# ZHSD-PL-CONNS.net
KiCad netlist of a schematic drawn in Altium Designer
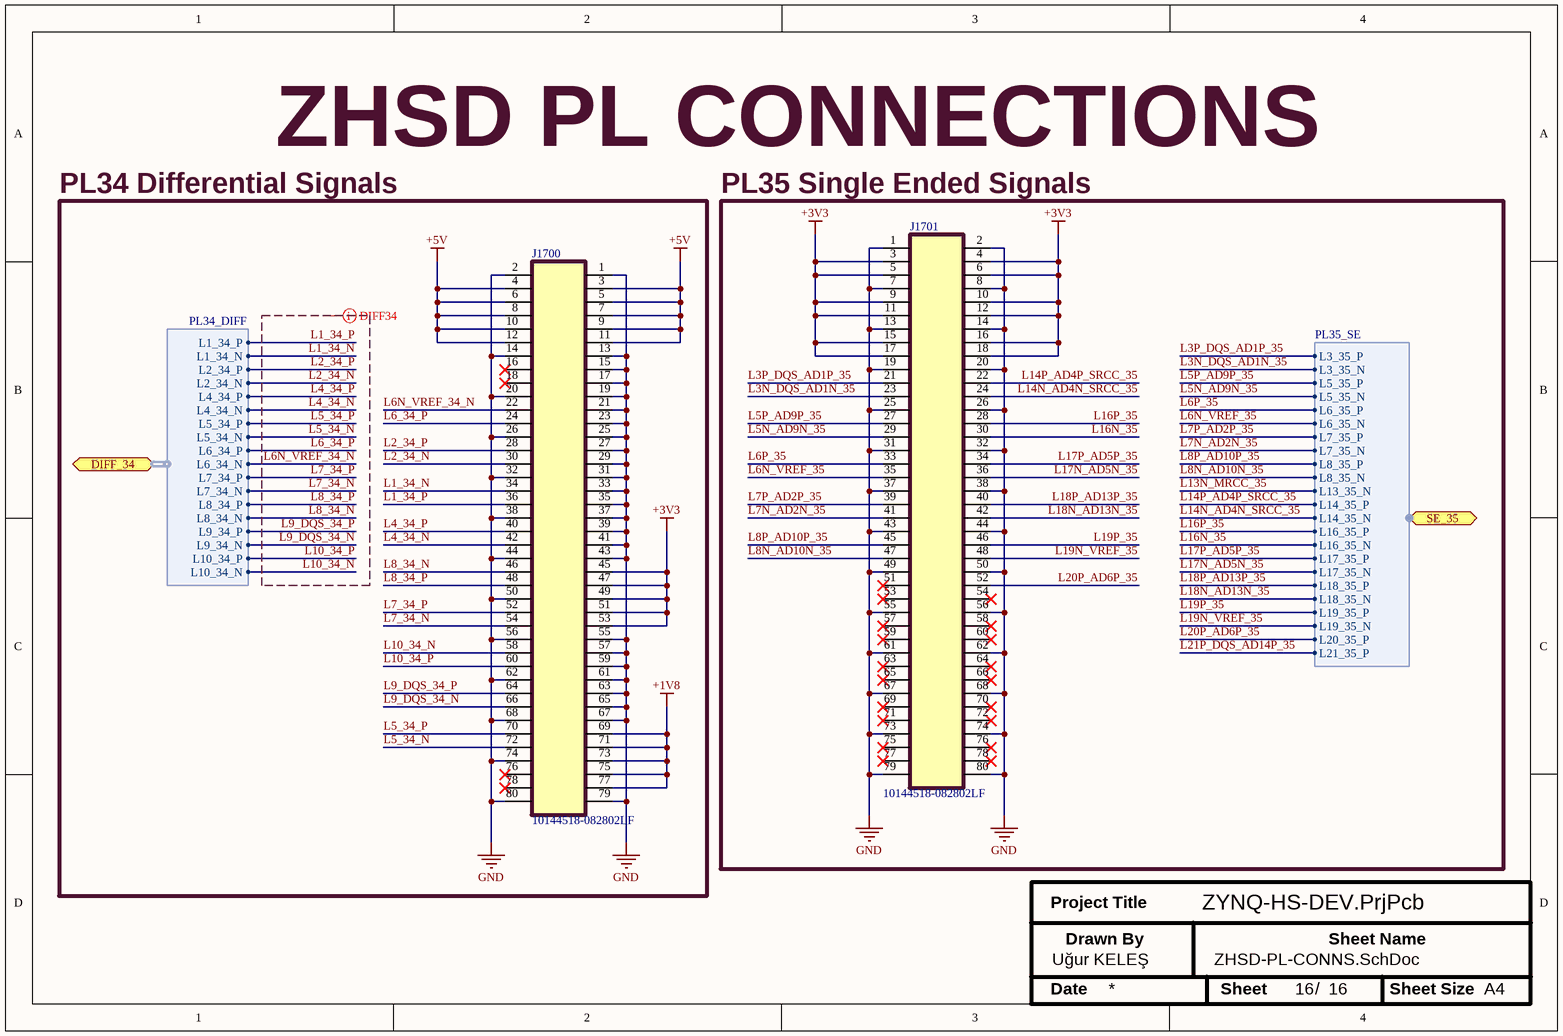
[diagram p0: ZHSD-PL-CONNS.SchDoc]

(export (version "E")
  (design (tool "Eeschema 10.0.6"))
  (components
    (comp (ref "J1700")
      (value "10144518-082802LF")
      (footprint "10144518-082802LF")
      (description "BergStak® Lite 0.80mm, Board-to-Board Connector, 80 Positions, Dual Row, Vertical Header")
      (fields (field (name "MANUFACTURER") "Amphenol"))
      (libsource (lib "") (part "10144518-082802LF_1"))
    )
    (comp (ref "J1701")
      (value "10144518-082802LF")
      (footprint "10144518-082802LF")
      (description "BergStak® Lite 0.80mm, Board-to-Board Connector, 80 Positions, Dual Row, Vertical Header")
      (fields (field (name "MANUFACTURER") "Amphenol"))
      (libsource (lib "UK_Library") (part "10144518-082802LF"))
    )
  )
  (nets
    (net (code "3") (name "+1V8") (class "Default")
      (node (ref "J1700") (pin "69") (pintype "passive"))
      (node (ref "J1700") (pin "71") (pintype "passive"))
      (node (ref "J1700") (pin "73") (pintype "passive"))
      (node (ref "J1700") (pin "75") (pintype "passive"))
      (node (ref "J1700") (pin "77") (pintype "passive"))
    )
    (net (code "4") (name "+3V3") (class "Default")
      (node (ref "J1700") (pin "45") (pintype "passive"))
      (node (ref "J1700") (pin "47") (pintype "passive"))
      (node (ref "J1700") (pin "49") (pintype "passive"))
      (node (ref "J1700") (pin "51") (pintype "passive"))
      (node (ref "J1700") (pin "53") (pintype "passive"))
      (node (ref "J1701") (pin "10") (pintype "passive"))
      (node (ref "J1701") (pin "11") (pintype "passive"))
      (node (ref "J1701") (pin "12") (pintype "passive"))
      (node (ref "J1701") (pin "15") (pintype "passive"))
      (node (ref "J1701") (pin "16") (pintype "passive"))
      (node (ref "J1701") (pin "17") (pintype "passive"))
      (node (ref "J1701") (pin "18") (pintype "passive"))
      (node (ref "J1701") (pin "3") (pintype "passive"))
      (node (ref "J1701") (pin "4") (pintype "passive"))
      (node (ref "J1701") (pin "5") (pintype "passive"))
      (node (ref "J1701") (pin "6") (pintype "passive"))
      (node (ref "J1701") (pin "9") (pintype "passive"))
    )
    (net (code "5") (name "+5V") (class "Default")
      (node (ref "J1700") (pin "10") (pintype "passive"))
      (node (ref "J1700") (pin "11") (pintype "passive"))
      (node (ref "J1700") (pin "12") (pintype "passive"))
      (node (ref "J1700") (pin "3") (pintype "passive"))
      (node (ref "J1700") (pin "4") (pintype "passive"))
      (node (ref "J1700") (pin "5") (pintype "passive"))
      (node (ref "J1700") (pin "6") (pintype "passive"))
      (node (ref "J1700") (pin "7") (pintype "passive"))
      (node (ref "J1700") (pin "8") (pintype "passive"))
      (node (ref "J1700") (pin "9") (pintype "passive"))
    )
    (net (code "6") (name "/L1_34_N") (class "Default") (node (ref "J1700") (pin "34") (pintype "passive")))
    (net (code "7") (name "/L1_34_P") (class "Default") (node (ref "J1700") (pin "36") (pintype "passive")))
    (net (code "8") (name "/L2_34_N") (class "Default") (node (ref "J1700") (pin "30") (pintype "passive")))
    (net (code "9") (name "/L2_34_P") (class "Default") (node (ref "J1700") (pin "28") (pintype "passive")))
    (net (code "10") (name "/L3N_DQS_AD1N_35") (class "Default")
      (node (ref "J1701") (pin "23") (pintype "passive"))
    )
    (net (code "11") (name "/L3P_DQS_AD1P_35") (class "Default")
      (node (ref "J1701") (pin "21") (pintype "passive"))
    )
    (net (code "12") (name "/L4_34_N") (class "Default") (node (ref "J1700") (pin "42") (pintype "passive")))
    (net (code "13") (name "/L4_34_P") (class "Default") (node (ref "J1700") (pin "40") (pintype "passive")))
    (net (code "14") (name "/L5N_AD9N_35") (class "Default")
      (node (ref "J1701") (pin "29") (pintype "passive"))
    )
    (net (code "15") (name "/L5P_AD9P_35") (class "Default")
      (node (ref "J1701") (pin "27") (pintype "passive"))
    )
    (net (code "16") (name "/L5_34_N") (class "Default") (node (ref "J1700") (pin "72") (pintype "passive")))
    (net (code "17") (name "/L5_34_P") (class "Default") (node (ref "J1700") (pin "70") (pintype "passive")))
    (net (code "18") (name "/L6N_VREF_34_N") (class "Default")
      (node (ref "J1700") (pin "22") (pintype "passive"))
    )
    (net (code "19") (name "/L6N_VREF_35") (class "Default")
      (node (ref "J1701") (pin "35") (pintype "passive"))
    )
    (net (code "20") (name "/L6P_35") (class "Default") (node (ref "J1701") (pin "33") (pintype "passive")))
    (net (code "21") (name "/L6_34_P") (class "Default") (node (ref "J1700") (pin "24") (pintype "passive")))
    (net (code "22") (name "/L7N_AD2N_35") (class "Default")
      (node (ref "J1701") (pin "41") (pintype "passive"))
    )
    (net (code "23") (name "/L7P_AD2P_35") (class "Default")
      (node (ref "J1701") (pin "39") (pintype "passive"))
    )
    (net (code "24") (name "/L7_34_N") (class "Default") (node (ref "J1700") (pin "54") (pintype "passive")))
    (net (code "25") (name "/L7_34_P") (class "Default") (node (ref "J1700") (pin "52") (pintype "passive")))
    (net (code "26") (name "/L8N_AD10N_35") (class "Default")
      (node (ref "J1701") (pin "47") (pintype "passive"))
    )
    (net (code "27") (name "/L8P_AD10P_35") (class "Default")
      (node (ref "J1701") (pin "45") (pintype "passive"))
    )
    (net (code "28") (name "/L8_34_N") (class "Default") (node (ref "J1700") (pin "46") (pintype "passive")))
    (net (code "29") (name "/L8_34_P") (class "Default") (node (ref "J1700") (pin "48") (pintype "passive")))
    (net (code "30") (name "/L9_DQS_34_N") (class "Default")
      (node (ref "J1700") (pin "66") (pintype "passive"))
    )
    (net (code "31") (name "/L9_DQS_34_P") (class "Default")
      (node (ref "J1700") (pin "64") (pintype "passive"))
    )
    (net (code "32") (name "/L10_34_N") (class "Default") (node (ref "J1700") (pin "58") (pintype "passive")))
    (net (code "33") (name "/L10_34_P") (class "Default") (node (ref "J1700") (pin "60") (pintype "passive")))
    (net (code "35") (name "/L14N_AD4N_SRCC_35") (class "Default")
      (node (ref "J1701") (pin "24") (pintype "passive"))
    )
    (net (code "36") (name "/L14P_AD4P_SRCC_35") (class "Default")
      (node (ref "J1701") (pin "22") (pintype "passive"))
    )
    (net (code "37") (name "/L16N_35") (class "Default") (node (ref "J1701") (pin "30") (pintype "passive")))
    (net (code "38") (name "/L16P_35") (class "Default") (node (ref "J1701") (pin "28") (pintype "passive")))
    (net (code "39") (name "/L17N_AD5N_35") (class "Default")
      (node (ref "J1701") (pin "36") (pintype "passive"))
    )
    (net (code "40") (name "/L17P_AD5P_35") (class "Default")
      (node (ref "J1701") (pin "34") (pintype "passive"))
    )
    (net (code "41") (name "/L18N_AD13N_35") (class "Default")
      (node (ref "J1701") (pin "42") (pintype "passive"))
    )
    (net (code "42") (name "/L18P_AD13P_35") (class "Default")
      (node (ref "J1701") (pin "40") (pintype "passive"))
    )
    (net (code "43") (name "/L19N_VREF_35") (class "Default")
      (node (ref "J1701") (pin "48") (pintype "passive"))
    )
    (net (code "44") (name "/L19P_35") (class "Default") (node (ref "J1701") (pin "46") (pintype "passive")))
    (net (code "45") (name "/L20P_AD6P_35") (class "Default")
      (node (ref "J1701") (pin "52") (pintype "passive"))
    )
    (net (code "49") (name "GND") (class "Default")
      (node (ref "J1700") (pin "1") (pintype "passive"))
      (node (ref "J1700") (pin "13") (pintype "passive"))
      (node (ref "J1700") (pin "14") (pintype "passive"))
      (node (ref "J1700") (pin "15") (pintype "passive"))
      (node (ref "J1700") (pin "17") (pintype "passive"))
      (node (ref "J1700") (pin "19") (pintype "passive"))
      (node (ref "J1700") (pin "2") (pintype "passive"))
      (node (ref "J1700") (pin "20") (pintype "passive"))
      (node (ref "J1700") (pin "21") (pintype "passive"))
      (node (ref "J1700") (pin "23") (pintype "passive"))
      (node (ref "J1700") (pin "25") (pintype "passive"))
      (node (ref "J1700") (pin "26") (pintype "passive"))
      (node (ref "J1700") (pin "27") (pintype "passive"))
      (node (ref "J1700") (pin "29") (pintype "passive"))
      (node (ref "J1700") (pin "31") (pintype "passive"))
      (node (ref "J1700") (pin "32") (pintype "passive"))
      (node (ref "J1700") (pin "33") (pintype "passive"))
      (node (ref "J1700") (pin "35") (pintype "passive"))
      (node (ref "J1700") (pin "37") (pintype "passive"))
      (node (ref "J1700") (pin "38") (pintype "passive"))
      (node (ref "J1700") (pin "39") (pintype "passive"))
      (node (ref "J1700") (pin "41") (pintype "passive"))
      (node (ref "J1700") (pin "43") (pintype "passive"))
      (node (ref "J1700") (pin "44") (pintype "passive"))
      (node (ref "J1700") (pin "50") (pintype "passive"))
      (node (ref "J1700") (pin "55") (pintype "passive"))
      (node (ref "J1700") (pin "56") (pintype "passive"))
      (node (ref "J1700") (pin "57") (pintype "passive"))
      (node (ref "J1700") (pin "59") (pintype "passive"))
      (node (ref "J1700") (pin "61") (pintype "passive"))
      (node (ref "J1700") (pin "62") (pintype "passive"))
      (node (ref "J1700") (pin "63") (pintype "passive"))
      (node (ref "J1700") (pin "65") (pintype "passive"))
      (node (ref "J1700") (pin "67") (pintype "passive"))
      (node (ref "J1700") (pin "68") (pintype "passive"))
      (node (ref "J1700") (pin "74") (pintype "passive"))
      (node (ref "J1700") (pin "79") (pintype "passive"))
      (node (ref "J1700") (pin "80") (pintype "passive"))
      (node (ref "J1701") (pin "1") (pintype "passive"))
      (node (ref "J1701") (pin "13") (pintype "passive"))
      (node (ref "J1701") (pin "14") (pintype "passive"))
      (node (ref "J1701") (pin "19") (pintype "passive"))
      (node (ref "J1701") (pin "2") (pintype "passive"))
      (node (ref "J1701") (pin "20") (pintype "passive"))
      (node (ref "J1701") (pin "25") (pintype "passive"))
      (node (ref "J1701") (pin "26") (pintype "passive"))
      (node (ref "J1701") (pin "31") (pintype "passive"))
      (node (ref "J1701") (pin "32") (pintype "passive"))
      (node (ref "J1701") (pin "37") (pintype "passive"))
      (node (ref "J1701") (pin "38") (pintype "passive"))
      (node (ref "J1701") (pin "43") (pintype "passive"))
      (node (ref "J1701") (pin "44") (pintype "passive"))
      (node (ref "J1701") (pin "49") (pintype "passive"))
      (node (ref "J1701") (pin "50") (pintype "passive"))
      (node (ref "J1701") (pin "55") (pintype "passive"))
      (node (ref "J1701") (pin "56") (pintype "passive"))
      (node (ref "J1701") (pin "61") (pintype "passive"))
      (node (ref "J1701") (pin "62") (pintype "passive"))
      (node (ref "J1701") (pin "67") (pintype "passive"))
      (node (ref "J1701") (pin "68") (pintype "passive"))
      (node (ref "J1701") (pin "7") (pintype "passive"))
      (node (ref "J1701") (pin "73") (pintype "passive"))
      (node (ref "J1701") (pin "74") (pintype "passive"))
      (node (ref "J1701") (pin "79") (pintype "passive"))
      (node (ref "J1701") (pin "8") (pintype "passive"))
      (node (ref "J1701") (pin "80") (pintype "passive"))
    )
    (net (code "50") (name "unconnected-(J1700-Pad16)") (class "Default")
      (node (ref "J1700") (pin "16") (pintype "passive+no_connect"))
    )
    (net (code "51") (name "unconnected-(J1700-Pad18)") (class "Default")
      (node (ref "J1700") (pin "18") (pintype "passive+no_connect"))
    )
    (net (code "52") (name "unconnected-(J1700-Pad76)") (class "Default")
      (node (ref "J1700") (pin "76") (pintype "passive+no_connect"))
    )
    (net (code "53") (name "unconnected-(J1700-Pad78)") (class "Default")
      (node (ref "J1700") (pin "78") (pintype "passive+no_connect"))
    )
    (net (code "54") (name "unconnected-(J1701-Pad51)") (class "Default")
      (node (ref "J1701") (pin "51") (pintype "passive+no_connect"))
    )
    (net (code "55") (name "unconnected-(J1701-Pad53)") (class "Default")
      (node (ref "J1701") (pin "53") (pintype "passive+no_connect"))
    )
    (net (code "56") (name "unconnected-(J1701-Pad54)") (class "Default")
      (node (ref "J1701") (pin "54") (pintype "passive+no_connect"))
    )
    (net (code "57") (name "unconnected-(J1701-Pad57)") (class "Default")
      (node (ref "J1701") (pin "57") (pintype "passive+no_connect"))
    )
    (net (code "58") (name "unconnected-(J1701-Pad58)") (class "Default")
      (node (ref "J1701") (pin "58") (pintype "passive+no_connect"))
    )
    (net (code "59") (name "unconnected-(J1701-Pad59)") (class "Default")
      (node (ref "J1701") (pin "59") (pintype "passive+no_connect"))
    )
    (net (code "60") (name "unconnected-(J1701-Pad60)") (class "Default")
      (node (ref "J1701") (pin "60") (pintype "passive+no_connect"))
    )
    (net (code "61") (name "unconnected-(J1701-Pad63)") (class "Default")
      (node (ref "J1701") (pin "63") (pintype "passive+no_connect"))
    )
    (net (code "62") (name "unconnected-(J1701-Pad64)") (class "Default")
      (node (ref "J1701") (pin "64") (pintype "passive+no_connect"))
    )
    (net (code "63") (name "unconnected-(J1701-Pad65)") (class "Default")
      (node (ref "J1701") (pin "65") (pintype "passive+no_connect"))
    )
    (net (code "64") (name "unconnected-(J1701-Pad66)") (class "Default")
      (node (ref "J1701") (pin "66") (pintype "passive+no_connect"))
    )
    (net (code "65") (name "unconnected-(J1701-Pad69)") (class "Default")
      (node (ref "J1701") (pin "69") (pintype "passive+no_connect"))
    )
    (net (code "66") (name "unconnected-(J1701-Pad70)") (class "Default")
      (node (ref "J1701") (pin "70") (pintype "passive+no_connect"))
    )
    (net (code "67") (name "unconnected-(J1701-Pad71)") (class "Default")
      (node (ref "J1701") (pin "71") (pintype "passive+no_connect"))
    )
    (net (code "68") (name "unconnected-(J1701-Pad72)") (class "Default")
      (node (ref "J1701") (pin "72") (pintype "passive+no_connect"))
    )
    (net (code "69") (name "unconnected-(J1701-Pad75)") (class "Default")
      (node (ref "J1701") (pin "75") (pintype "passive+no_connect"))
    )
    (net (code "70") (name "unconnected-(J1701-Pad76)") (class "Default")
      (node (ref "J1701") (pin "76") (pintype "passive+no_connect"))
    )
    (net (code "71") (name "unconnected-(J1701-Pad77)") (class "Default")
      (node (ref "J1701") (pin "77") (pintype "passive+no_connect"))
    )
    (net (code "72") (name "unconnected-(J1701-Pad78)") (class "Default")
      (node (ref "J1701") (pin "78") (pintype "passive+no_connect"))
    )
  )
)
